# FLIC_V2.net
KiCad netlist of a schematic drawn in EAGLE
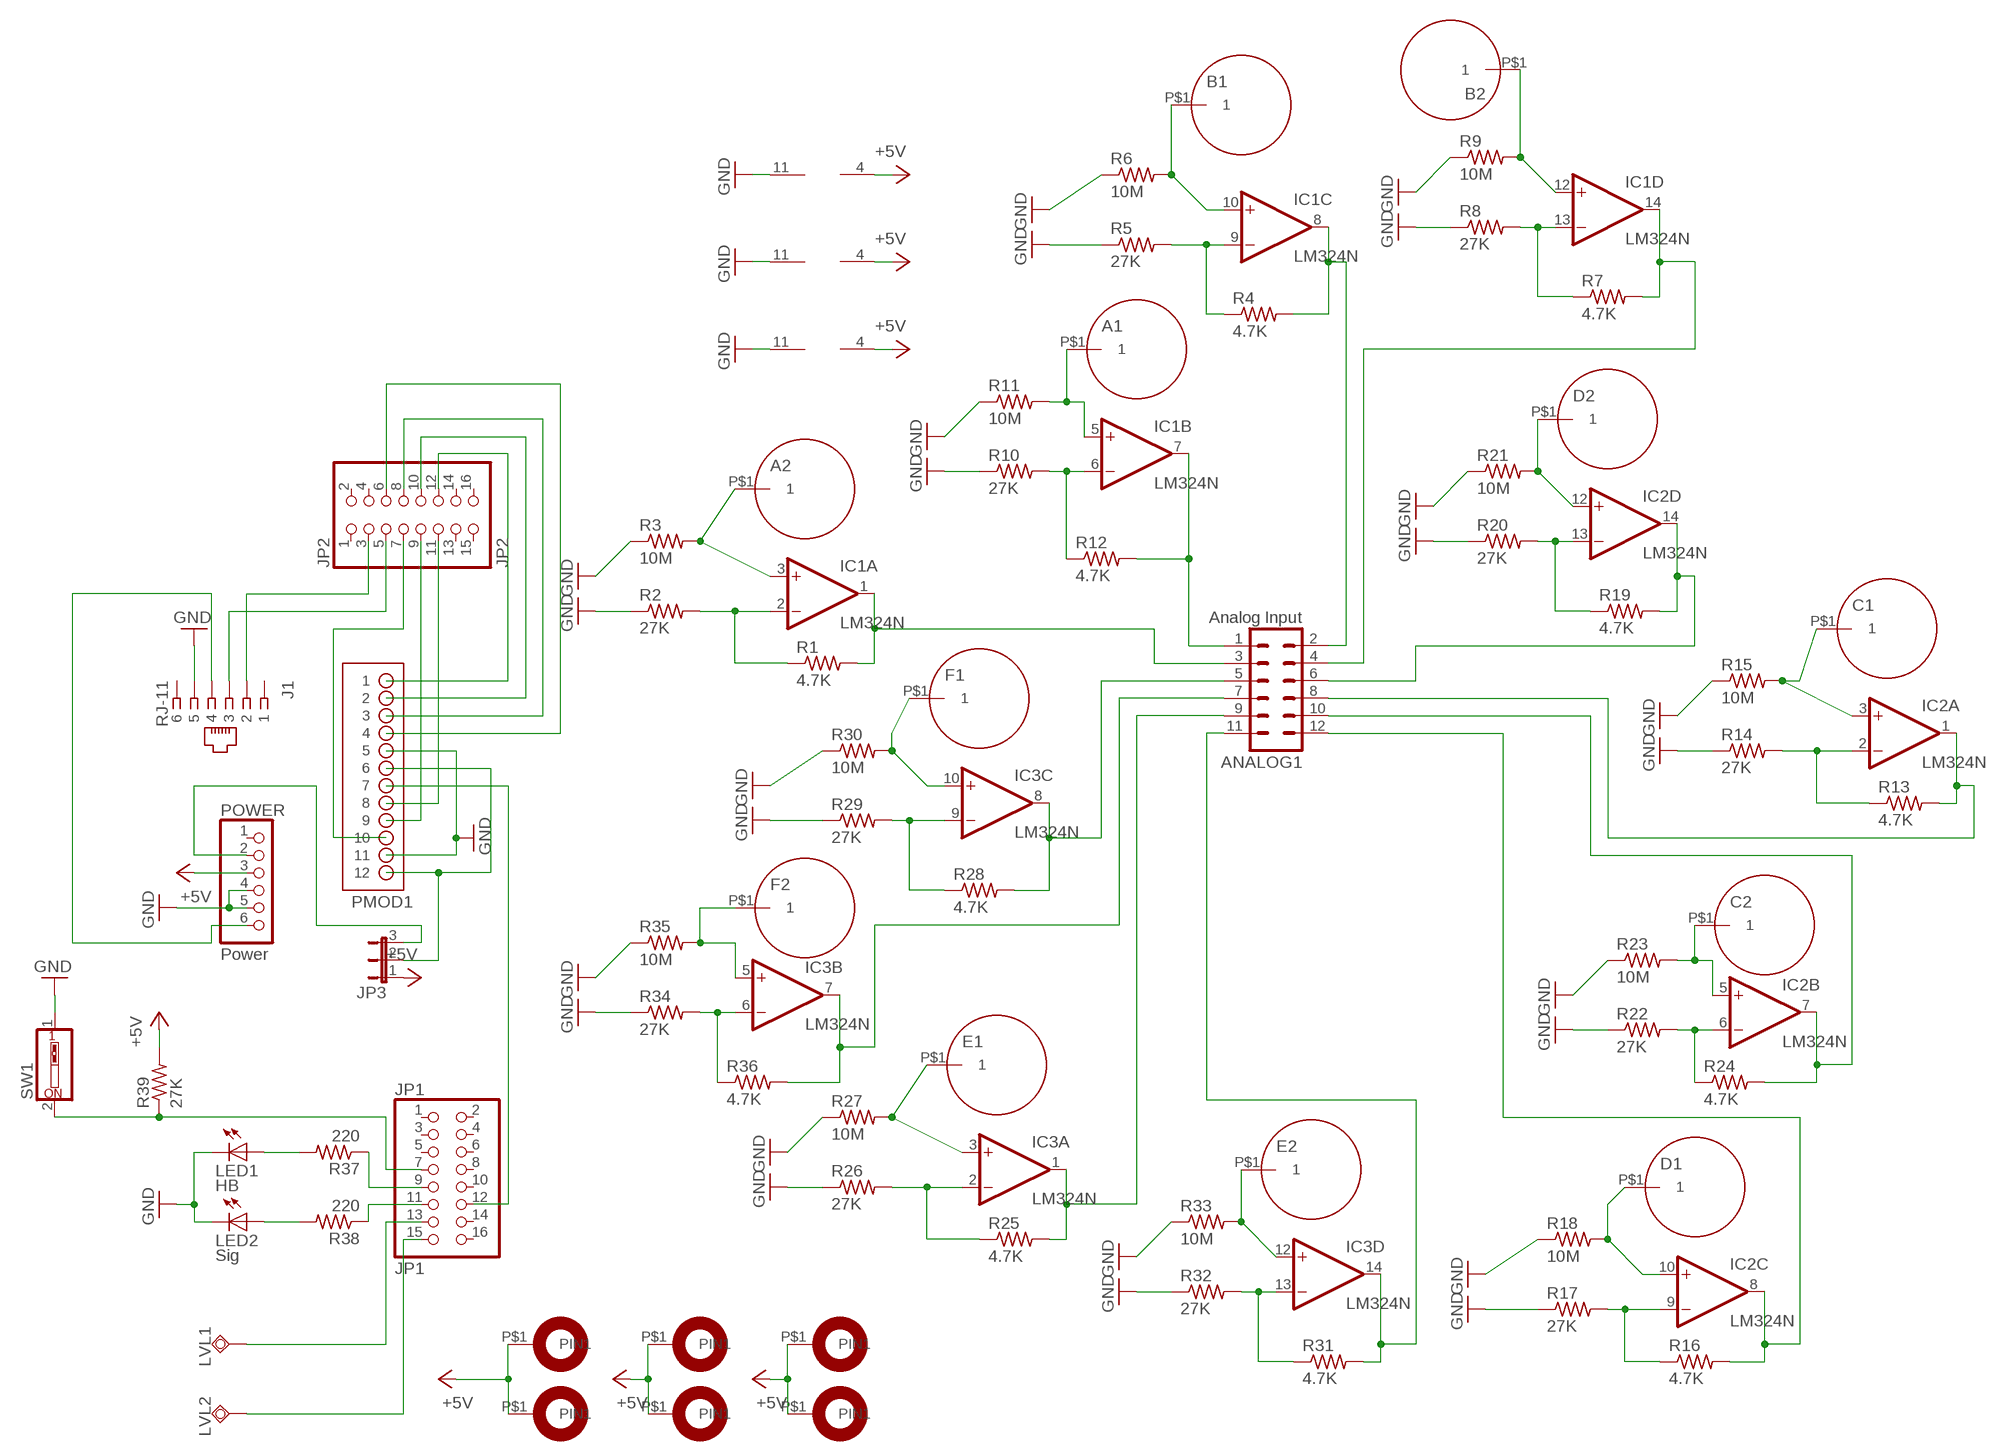
[diagram p0: schematic, sheet 1]

(export (version "E")
  (design (tool "Eeschema 10.0.6"))
  (components
    (comp (ref "A1")
      (value "FLIC_PADPAD")
      (footprint "eagle-import:FLICPAD")
      (libsource (lib "eagle-import") (part "FLIC_PADPAD"))
    )
    (comp (ref "A2")
      (value "FLIC_PADPAD")
      (footprint "eagle-import:FLICPAD")
      (libsource (lib "eagle-import") (part "FLIC_PADPAD"))
    )
    (comp (ref "ANALOG1")
      (value "Analog Input")
      (footprint "eagle-import:MA06-2")
      (libsource (lib "eagle-import") (part "MA06-2"))
    )
    (comp (ref "B1")
      (value "FLIC_PADPAD")
      (footprint "eagle-import:FLICPAD")
      (libsource (lib "eagle-import") (part "FLIC_PADPAD"))
    )
    (comp (ref "B2")
      (value "FLIC_PADPAD")
      (footprint "eagle-import:FLICPAD")
      (libsource (lib "eagle-import") (part "FLIC_PADPAD"))
    )
    (comp (ref "C1")
      (value "FLIC_PADPAD")
      (footprint "eagle-import:FLICPAD")
      (libsource (lib "eagle-import") (part "FLIC_PADPAD"))
    )
    (comp (ref "C2")
      (value "FLIC_PADPAD")
      (footprint "eagle-import:FLICPAD")
      (libsource (lib "eagle-import") (part "FLIC_PADPAD"))
    )
    (comp (ref "D1")
      (value "FLIC_PADPAD")
      (footprint "eagle-import:FLICPAD")
      (libsource (lib "eagle-import") (part "FLIC_PADPAD"))
    )
    (comp (ref "D2")
      (value "FLIC_PADPAD")
      (footprint "eagle-import:FLICPAD")
      (libsource (lib "eagle-import") (part "FLIC_PADPAD"))
    )
    (comp (ref "E1")
      (value "FLIC_PADPAD")
      (footprint "eagle-import:FLICPAD")
      (libsource (lib "eagle-import") (part "FLIC_PADPAD"))
    )
    (comp (ref "E2")
      (value "FLIC_PADPAD")
      (footprint "eagle-import:FLICPAD")
      (libsource (lib "eagle-import") (part "FLIC_PADPAD"))
    )
    (comp (ref "F1")
      (value "FLIC_PADPAD")
      (footprint "eagle-import:FLICPAD")
      (libsource (lib "eagle-import") (part "FLIC_PADPAD"))
    )
    (comp (ref "F2")
      (value "FLIC_PADPAD")
      (footprint "eagle-import:FLICPAD")
      (libsource (lib "eagle-import") (part "FLIC_PADPAD"))
    )
    (comp (ref "IC1")
      (value "LM324N")
      (footprint "eagle-import:DIL14")
      (libsource (lib "eagle-import") (part "LM324N"))
    )
    (comp (ref "IC2")
      (value "LM324N")
      (footprint "eagle-import:DIL14")
      (libsource (lib "eagle-import") (part "LM324N"))
    )
    (comp (ref "IC3")
      (value "LM324N")
      (footprint "eagle-import:DIL14")
      (libsource (lib "eagle-import") (part "LM324N"))
    )
    (comp (ref "J1")
      (value "RJ-11")
      (footprint "eagle-import:RJ11-NO_SHIELD")
      (fields (field (name "MF") "TYCO ELECTRONICS") (field (name "MPN") "RJ11-2L-B"))
      (libsource (lib "eagle-import") (part "RJ11-2L-B"))
    )
    (comp (ref "JP1")
      (value "JP1")
      (footprint "eagle-import:2X08")
      (libsource (lib "eagle-import") (part "PINHD-2X8"))
    )
    (comp (ref "JP2")
      (value "JP2")
      (footprint "eagle-import:2X08")
      (libsource (lib "eagle-import") (part "PINHD-2X8"))
    )
    (comp (ref "JP3")
      (value "JP2E")
      (footprint "eagle-import:JP2")
      (libsource (lib "eagle-import") (part "JP2E"))
    )
    (comp (ref "LED1")
      (value "HB")
      (footprint "eagle-import:LED3MM")
      (libsource (lib "eagle-import") (part "LED3MM"))
    )
    (comp (ref "LED2")
      (value "Sig")
      (footprint "eagle-import:LED3MM")
      (libsource (lib "eagle-import") (part "LED3MM"))
    )
    (comp (ref "LVL1")
      (value "TPSQTP20R")
      (footprint "eagle-import:TP20R")
      (libsource (lib "eagle-import") (part "TPSQTP20R"))
    )
    (comp (ref "LVL2")
      (value "TPSQTP20R")
      (footprint "eagle-import:TP20R")
      (libsource (lib "eagle-import") (part "TPSQTP20R"))
    )
    (comp (ref "PMOD1")
      (value "PMOD-2X6-S")
      (footprint "eagle-import:PMOD-2X6-S")
      (libsource (lib "eagle-import") (part "PMOD-2X6-S"))
    )
    (comp (ref "POWER")
      (value "Power")
      (footprint "eagle-import:1X06")
      (libsource (lib "eagle-import") (part "PINHD-1X6"))
    )
    (comp (ref "R1")
      (value "4.7K")
      (footprint "eagle-import:0207_10")
      (libsource (lib "eagle-import") (part "R-US_0207/10"))
    )
    (comp (ref "R2")
      (value "27K")
      (footprint "eagle-import:0207_10")
      (libsource (lib "eagle-import") (part "R-US_0207/10"))
    )
    (comp (ref "R3")
      (value "10M")
      (footprint "eagle-import:0207_10")
      (libsource (lib "eagle-import") (part "R-US_0207/10"))
    )
    (comp (ref "R4")
      (value "4.7K")
      (footprint "eagle-import:0207_10")
      (libsource (lib "eagle-import") (part "R-US_0207/10"))
    )
    (comp (ref "R5")
      (value "27K")
      (footprint "eagle-import:0207_10")
      (libsource (lib "eagle-import") (part "R-US_0207/10"))
    )
    (comp (ref "R6")
      (value "10M")
      (footprint "eagle-import:0207_10")
      (libsource (lib "eagle-import") (part "R-US_0207/10"))
    )
    (comp (ref "R7")
      (value "4.7K")
      (footprint "eagle-import:0207_10")
      (libsource (lib "eagle-import") (part "R-US_0207/10"))
    )
    (comp (ref "R8")
      (value "27K")
      (footprint "eagle-import:0207_10")
      (libsource (lib "eagle-import") (part "R-US_0207/10"))
    )
    (comp (ref "R9")
      (value "10M")
      (footprint "eagle-import:0207_10")
      (libsource (lib "eagle-import") (part "R-US_0207/10"))
    )
    (comp (ref "R10")
      (value "27K")
      (footprint "eagle-import:0207_10")
      (libsource (lib "eagle-import") (part "R-US_0207/10"))
    )
    (comp (ref "R11")
      (value "10M")
      (footprint "eagle-import:0207_10")
      (libsource (lib "eagle-import") (part "R-US_0207/10"))
    )
    (comp (ref "R12")
      (value "4.7K")
      (footprint "eagle-import:0207_10")
      (libsource (lib "eagle-import") (part "R-US_0207/10"))
    )
    (comp (ref "R13")
      (value "4.7K")
      (footprint "eagle-import:0207_10")
      (libsource (lib "eagle-import") (part "R-US_0207/10"))
    )
    (comp (ref "R14")
      (value "27K")
      (footprint "eagle-import:0207_10")
      (libsource (lib "eagle-import") (part "R-US_0207/10"))
    )
    (comp (ref "R15")
      (value "10M")
      (footprint "eagle-import:0207_10")
      (libsource (lib "eagle-import") (part "R-US_0207/10"))
    )
    (comp (ref "R16")
      (value "4.7K")
      (footprint "eagle-import:0207_10")
      (libsource (lib "eagle-import") (part "R-US_0207/10"))
    )
    (comp (ref "R17")
      (value "27K")
      (footprint "eagle-import:0207_10")
      (libsource (lib "eagle-import") (part "R-US_0207/10"))
    )
    (comp (ref "R18")
      (value "10M")
      (footprint "eagle-import:0207_10")
      (libsource (lib "eagle-import") (part "R-US_0207/10"))
    )
    (comp (ref "R19")
      (value "4.7K")
      (footprint "eagle-import:0207_10")
      (libsource (lib "eagle-import") (part "R-US_0207/10"))
    )
    (comp (ref "R20")
      (value "27K")
      (footprint "eagle-import:0207_10")
      (libsource (lib "eagle-import") (part "R-US_0207/10"))
    )
    (comp (ref "R21")
      (value "10M")
      (footprint "eagle-import:0207_10")
      (libsource (lib "eagle-import") (part "R-US_0207/10"))
    )
    (comp (ref "R22")
      (value "27K")
      (footprint "eagle-import:0207_10")
      (libsource (lib "eagle-import") (part "R-US_0207/10"))
    )
    (comp (ref "R23")
      (value "10M")
      (footprint "eagle-import:0207_10")
      (libsource (lib "eagle-import") (part "R-US_0207/10"))
    )
    (comp (ref "R24")
      (value "4.7K")
      (footprint "eagle-import:0207_10")
      (libsource (lib "eagle-import") (part "R-US_0207/10"))
    )
    (comp (ref "R25")
      (value "4.7K")
      (footprint "eagle-import:0207_10")
      (libsource (lib "eagle-import") (part "R-US_0207/10"))
    )
    (comp (ref "R26")
      (value "27K")
      (footprint "eagle-import:0207_10")
      (libsource (lib "eagle-import") (part "R-US_0207/10"))
    )
    (comp (ref "R27")
      (value "10M")
      (footprint "eagle-import:0207_10")
      (libsource (lib "eagle-import") (part "R-US_0207/10"))
    )
    (comp (ref "R28")
      (value "4.7K")
      (footprint "eagle-import:0207_10")
      (libsource (lib "eagle-import") (part "R-US_0207/10"))
    )
    (comp (ref "R29")
      (value "27K")
      (footprint "eagle-import:0207_10")
      (libsource (lib "eagle-import") (part "R-US_0207/10"))
    )
    (comp (ref "R30")
      (value "10M")
      (footprint "eagle-import:0207_10")
      (libsource (lib "eagle-import") (part "R-US_0207/10"))
    )
    (comp (ref "R31")
      (value "4.7K")
      (footprint "eagle-import:0207_10")
      (libsource (lib "eagle-import") (part "R-US_0207/10"))
    )
    (comp (ref "R32")
      (value "27K")
      (footprint "eagle-import:0207_10")
      (libsource (lib "eagle-import") (part "R-US_0207/10"))
    )
    (comp (ref "R33")
      (value "10M")
      (footprint "eagle-import:0207_10")
      (libsource (lib "eagle-import") (part "R-US_0207/10"))
    )
    (comp (ref "R34")
      (value "27K")
      (footprint "eagle-import:0207_10")
      (libsource (lib "eagle-import") (part "R-US_0207/10"))
    )
    (comp (ref "R35")
      (value "10M")
      (footprint "eagle-import:0207_10")
      (libsource (lib "eagle-import") (part "R-US_0207/10"))
    )
    (comp (ref "R36")
      (value "4.7K")
      (footprint "eagle-import:0207_10")
      (libsource (lib "eagle-import") (part "R-US_0207/10"))
    )
    (comp (ref "R37")
      (value "220")
      (footprint "eagle-import:0207_10")
      (libsource (lib "eagle-import") (part "R-US_0207/10"))
    )
    (comp (ref "R38")
      (value "220")
      (footprint "eagle-import:0207_10")
      (libsource (lib "eagle-import") (part "R-US_0207/10"))
    )
    (comp (ref "R39")
      (value "27K")
      (footprint "eagle-import:0207_10")
      (libsource (lib "eagle-import") (part "R-US_0207/10"))
    )
    (comp (ref "SW1")
      (value "SW_DIP-1")
      (footprint "eagle-import:EDG-01")
      (libsource (lib "eagle-import") (part "SW_DIP-1"))
    )
    (comp (ref "U$1")
      (value "4MM_HOLEA")
      (footprint "eagle-import:4MM")
      (libsource (lib "eagle-import") (part "4MM_HOLEA"))
    )
    (comp (ref "U$2")
      (value "4MM_HOLEA")
      (footprint "eagle-import:4MM")
      (libsource (lib "eagle-import") (part "4MM_HOLEA"))
    )
    (comp (ref "U$3")
      (value "4MM_HOLEA")
      (footprint "eagle-import:4MM")
      (libsource (lib "eagle-import") (part "4MM_HOLEA"))
    )
    (comp (ref "U$4")
      (value "4MM_HOLEA")
      (footprint "eagle-import:4MM")
      (libsource (lib "eagle-import") (part "4MM_HOLEA"))
    )
    (comp (ref "U$5")
      (value "4MM_HOLEA")
      (footprint "eagle-import:4MM")
      (libsource (lib "eagle-import") (part "4MM_HOLEA"))
    )
    (comp (ref "U$6")
      (value "4MM_HOLEA")
      (footprint "eagle-import:4MM")
      (libsource (lib "eagle-import") (part "4MM_HOLEA"))
    )
  )
  (nets
    (net (code "1") (name "+5V") (class "Default")
      (node (ref "IC1") (pin "4") (pinfunction "V+_4") (pintype "power_in"))
      (node (ref "IC2") (pin "4") (pinfunction "V+_4") (pintype "power_in"))
      (node (ref "IC3") (pin "4") (pinfunction "V+_4") (pintype "power_in"))
      (node (ref "JP3") (pin "1") (pinfunction "1_1") (pintype "passive"))
      (node (ref "POWER") (pin "3") (pinfunction "3_3") (pintype "passive"))
      (node (ref "R39") (pin "2") (pinfunction "2_2") (pintype "passive"))
      (node (ref "U$1") (pin "P$1") (pinfunction "PIN1_P$1") (pintype "bidirectional"))
      (node (ref "U$2") (pin "P$1") (pinfunction "PIN1_P$1") (pintype "bidirectional"))
      (node (ref "U$3") (pin "P$1") (pinfunction "PIN1_P$1") (pintype "bidirectional"))
      (node (ref "U$4") (pin "P$1") (pinfunction "PIN1_P$1") (pintype "bidirectional"))
      (node (ref "U$5") (pin "P$1") (pinfunction "PIN1_P$1") (pintype "bidirectional"))
      (node (ref "U$6") (pin "P$1") (pinfunction "PIN1_P$1") (pintype "bidirectional"))
    )
    (net (code "2") (name "GND") (class "Default")
      (node (ref "IC1") (pin "11") (pinfunction "V-_11") (pintype "power_in"))
      (node (ref "IC2") (pin "11") (pinfunction "V-_11") (pintype "power_in"))
      (node (ref "IC3") (pin "11") (pinfunction "V-_11") (pintype "power_in"))
      (node (ref "J1") (pin "5") (pinfunction "5_5") (pintype "passive"))
      (node (ref "LED1") (pin "K") (pinfunction "C_K") (pintype "passive"))
      (node (ref "LED2") (pin "K") (pinfunction "C_K") (pintype "passive"))
      (node (ref "PMOD1") (pin "11") (pinfunction "11_11") (pintype "passive"))
      (node (ref "PMOD1") (pin "5") (pinfunction "5_5") (pintype "passive"))
      (node (ref "POWER") (pin "4") (pinfunction "4_4") (pintype "passive"))
      (node (ref "POWER") (pin "5") (pinfunction "5_5") (pintype "passive"))
      (node (ref "R10") (pin "1") (pinfunction "1_1") (pintype "passive"))
      (node (ref "R11") (pin "1") (pinfunction "1_1") (pintype "passive"))
      (node (ref "R14") (pin "1") (pinfunction "1_1") (pintype "passive"))
      (node (ref "R15") (pin "1") (pinfunction "1_1") (pintype "passive"))
      (node (ref "R17") (pin "1") (pinfunction "1_1") (pintype "passive"))
      (node (ref "R18") (pin "1") (pinfunction "1_1") (pintype "passive"))
      (node (ref "R2") (pin "1") (pinfunction "1_1") (pintype "passive"))
      (node (ref "R20") (pin "1") (pinfunction "1_1") (pintype "passive"))
      (node (ref "R21") (pin "1") (pinfunction "1_1") (pintype "passive"))
      (node (ref "R22") (pin "1") (pinfunction "1_1") (pintype "passive"))
      (node (ref "R23") (pin "1") (pinfunction "1_1") (pintype "passive"))
      (node (ref "R26") (pin "1") (pinfunction "1_1") (pintype "passive"))
      (node (ref "R27") (pin "1") (pinfunction "1_1") (pintype "passive"))
      (node (ref "R29") (pin "1") (pinfunction "1_1") (pintype "passive"))
      (node (ref "R3") (pin "1") (pinfunction "1_1") (pintype "passive"))
      (node (ref "R30") (pin "1") (pinfunction "1_1") (pintype "passive"))
      (node (ref "R32") (pin "1") (pinfunction "1_1") (pintype "passive"))
      (node (ref "R33") (pin "1") (pinfunction "1_1") (pintype "passive"))
      (node (ref "R34") (pin "1") (pinfunction "1_1") (pintype "passive"))
      (node (ref "R35") (pin "1") (pinfunction "1_1") (pintype "passive"))
      (node (ref "R5") (pin "1") (pinfunction "1_1") (pintype "passive"))
      (node (ref "R6") (pin "1") (pinfunction "1_1") (pintype "passive"))
      (node (ref "R8") (pin "1") (pinfunction "1_1") (pintype "passive"))
      (node (ref "R9") (pin "1") (pinfunction "1_1") (pintype "passive"))
      (node (ref "SW1") (pin "1") (pinfunction "1_1") (pintype "passive"))
    )
    (net (code "3") (name "Net-(A1-1)") (class "Default")
      (node (ref "A1") (pin "P$1") (pinfunction "1_P$1") (pintype "passive"))
      (node (ref "IC1") (pin "5") (pinfunction "+IN_5") (pintype "input"))
      (node (ref "R11") (pin "2") (pinfunction "2_2") (pintype "passive"))
    )
    (net (code "4") (name "Net-(A2-1)") (class "Default")
      (node (ref "A2") (pin "P$1") (pinfunction "1_P$1") (pintype "passive"))
      (node (ref "IC1") (pin "3") (pinfunction "+IN_3") (pintype "input"))
      (node (ref "R3") (pin "2") (pinfunction "2_2") (pintype "passive"))
    )
    (net (code "5") (name "Net-(B1-1)") (class "Default")
      (node (ref "B1") (pin "P$1") (pinfunction "1_P$1") (pintype "passive"))
      (node (ref "IC1") (pin "10") (pinfunction "+IN_10") (pintype "input"))
      (node (ref "R6") (pin "2") (pinfunction "2_2") (pintype "passive"))
    )
    (net (code "6") (name "Net-(B2-1)") (class "Default")
      (node (ref "B2") (pin "P$1") (pinfunction "1_P$1") (pintype "passive"))
      (node (ref "IC1") (pin "12") (pinfunction "+IN_12") (pintype "input"))
      (node (ref "R9") (pin "2") (pinfunction "2_2") (pintype "passive"))
    )
    (net (code "7") (name "Net-(C1-1)") (class "Default")
      (node (ref "C1") (pin "P$1") (pinfunction "1_P$1") (pintype "passive"))
      (node (ref "IC2") (pin "3") (pinfunction "+IN_3") (pintype "input"))
      (node (ref "R15") (pin "2") (pinfunction "2_2") (pintype "passive"))
    )
    (net (code "8") (name "Net-(C2-1)") (class "Default")
      (node (ref "C2") (pin "P$1") (pinfunction "1_P$1") (pintype "passive"))
      (node (ref "IC2") (pin "5") (pinfunction "+IN_5") (pintype "input"))
      (node (ref "R23") (pin "2") (pinfunction "2_2") (pintype "passive"))
    )
    (net (code "9") (name "Net-(D1-1)") (class "Default")
      (node (ref "D1") (pin "P$1") (pinfunction "1_P$1") (pintype "passive"))
      (node (ref "IC2") (pin "10") (pinfunction "+IN_10") (pintype "input"))
      (node (ref "R18") (pin "2") (pinfunction "2_2") (pintype "passive"))
    )
    (net (code "10") (name "Net-(D2-1)") (class "Default")
      (node (ref "D2") (pin "P$1") (pinfunction "1_P$1") (pintype "passive"))
      (node (ref "IC2") (pin "12") (pinfunction "+IN_12") (pintype "input"))
      (node (ref "R21") (pin "2") (pinfunction "2_2") (pintype "passive"))
    )
    (net (code "11") (name "Net-(E1-1)") (class "Default")
      (node (ref "E1") (pin "P$1") (pinfunction "1_P$1") (pintype "passive"))
      (node (ref "IC3") (pin "3") (pinfunction "+IN_3") (pintype "input"))
      (node (ref "R27") (pin "2") (pinfunction "2_2") (pintype "passive"))
    )
    (net (code "12") (name "Net-(E2-1)") (class "Default")
      (node (ref "E2") (pin "P$1") (pinfunction "1_P$1") (pintype "passive"))
      (node (ref "IC3") (pin "12") (pinfunction "+IN_12") (pintype "input"))
      (node (ref "R33") (pin "2") (pinfunction "2_2") (pintype "passive"))
    )
    (net (code "13") (name "Net-(F1-1)") (class "Default")
      (node (ref "F1") (pin "P$1") (pinfunction "1_P$1") (pintype "passive"))
      (node (ref "IC3") (pin "10") (pinfunction "+IN_10") (pintype "input"))
      (node (ref "R30") (pin "2") (pinfunction "2_2") (pintype "passive"))
    )
    (net (code "14") (name "Net-(F2-1)") (class "Default")
      (node (ref "F2") (pin "P$1") (pinfunction "1_P$1") (pintype "passive"))
      (node (ref "IC3") (pin "5") (pinfunction "+IN_5") (pintype "input"))
      (node (ref "R35") (pin "2") (pinfunction "2_2") (pintype "passive"))
    )
    (net (code "15") (name "Net-(IC1A--IN)") (class "Default")
      (node (ref "IC1") (pin "2") (pinfunction "-IN_2") (pintype "input"))
      (node (ref "R1") (pin "1") (pinfunction "1_1") (pintype "passive"))
      (node (ref "R2") (pin "2") (pinfunction "2_2") (pintype "passive"))
    )
    (net (code "16") (name "Net-(IC1A-OUT)") (class "Default")
      (node (ref "ANALOG1") (pin "3") (pinfunction "3_3") (pintype "passive"))
      (node (ref "IC1") (pin "1") (pinfunction "OUT_1") (pintype "output"))
      (node (ref "R1") (pin "2") (pinfunction "2_2") (pintype "passive"))
    )
    (net (code "17") (name "Net-(IC1B--IN)") (class "Default")
      (node (ref "IC1") (pin "6") (pinfunction "-IN_6") (pintype "input"))
      (node (ref "R10") (pin "2") (pinfunction "2_2") (pintype "passive"))
      (node (ref "R12") (pin "1") (pinfunction "1_1") (pintype "passive"))
    )
    (net (code "18") (name "Net-(IC1B-OUT)") (class "Default")
      (node (ref "ANALOG1") (pin "1") (pinfunction "1_1") (pintype "passive"))
      (node (ref "IC1") (pin "7") (pinfunction "OUT_7") (pintype "output"))
      (node (ref "R12") (pin "2") (pinfunction "2_2") (pintype "passive"))
    )
    (net (code "19") (name "Net-(IC1C--IN)") (class "Default")
      (node (ref "IC1") (pin "9") (pinfunction "-IN_9") (pintype "input"))
      (node (ref "R4") (pin "1") (pinfunction "1_1") (pintype "passive"))
      (node (ref "R5") (pin "2") (pinfunction "2_2") (pintype "passive"))
    )
    (net (code "20") (name "Net-(IC1C-OUT)") (class "Default")
      (node (ref "ANALOG1") (pin "2") (pinfunction "2_2") (pintype "passive"))
      (node (ref "IC1") (pin "8") (pinfunction "OUT_8") (pintype "output"))
      (node (ref "R4") (pin "2") (pinfunction "2_2") (pintype "passive"))
    )
    (net (code "21") (name "Net-(IC1D--IN)") (class "Default")
      (node (ref "IC1") (pin "13") (pinfunction "-IN_13") (pintype "input"))
      (node (ref "R7") (pin "1") (pinfunction "1_1") (pintype "passive"))
      (node (ref "R8") (pin "2") (pinfunction "2_2") (pintype "passive"))
    )
    (net (code "22") (name "Net-(IC1D-OUT)") (class "Default")
      (node (ref "ANALOG1") (pin "4") (pinfunction "4_4") (pintype "passive"))
      (node (ref "IC1") (pin "14") (pinfunction "OUT_14") (pintype "output"))
      (node (ref "R7") (pin "2") (pinfunction "2_2") (pintype "passive"))
    )
    (net (code "23") (name "Net-(IC2A--IN)") (class "Default")
      (node (ref "IC2") (pin "2") (pinfunction "-IN_2") (pintype "input"))
      (node (ref "R13") (pin "1") (pinfunction "1_1") (pintype "passive"))
      (node (ref "R14") (pin "2") (pinfunction "2_2") (pintype "passive"))
    )
    (net (code "24") (name "Net-(IC2A-OUT)") (class "Default")
      (node (ref "ANALOG1") (pin "8") (pinfunction "8_8") (pintype "passive"))
      (node (ref "IC2") (pin "1") (pinfunction "OUT_1") (pintype "output"))
      (node (ref "R13") (pin "2") (pinfunction "2_2") (pintype "passive"))
    )
    (net (code "25") (name "Net-(IC2B--IN)") (class "Default")
      (node (ref "IC2") (pin "6") (pinfunction "-IN_6") (pintype "input"))
      (node (ref "R22") (pin "2") (pinfunction "2_2") (pintype "passive"))
      (node (ref "R24") (pin "1") (pinfunction "1_1") (pintype "passive"))
    )
    (net (code "26") (name "Net-(IC2B-OUT)") (class "Default")
      (node (ref "ANALOG1") (pin "10") (pinfunction "10_10") (pintype "passive"))
      (node (ref "IC2") (pin "7") (pinfunction "OUT_7") (pintype "output"))
      (node (ref "R24") (pin "2") (pinfunction "2_2") (pintype "passive"))
    )
    (net (code "27") (name "Net-(IC2C--IN)") (class "Default")
      (node (ref "IC2") (pin "9") (pinfunction "-IN_9") (pintype "input"))
      (node (ref "R16") (pin "1") (pinfunction "1_1") (pintype "passive"))
      (node (ref "R17") (pin "2") (pinfunction "2_2") (pintype "passive"))
    )
    (net (code "28") (name "Net-(IC2C-OUT)") (class "Default")
      (node (ref "ANALOG1") (pin "12") (pinfunction "12_12") (pintype "passive"))
      (node (ref "IC2") (pin "8") (pinfunction "OUT_8") (pintype "output"))
      (node (ref "R16") (pin "2") (pinfunction "2_2") (pintype "passive"))
    )
    (net (code "29") (name "Net-(IC2D--IN)") (class "Default")
      (node (ref "IC2") (pin "13") (pinfunction "-IN_13") (pintype "input"))
      (node (ref "R19") (pin "1") (pinfunction "1_1") (pintype "passive"))
      (node (ref "R20") (pin "2") (pinfunction "2_2") (pintype "passive"))
    )
    (net (code "30") (name "Net-(IC2D-OUT)") (class "Default")
      (node (ref "ANALOG1") (pin "6") (pinfunction "6_6") (pintype "passive"))
      (node (ref "IC2") (pin "14") (pinfunction "OUT_14") (pintype "output"))
      (node (ref "R19") (pin "2") (pinfunction "2_2") (pintype "passive"))
    )
    (net (code "31") (name "Net-(IC3A--IN)") (class "Default")
      (node (ref "IC3") (pin "2") (pinfunction "-IN_2") (pintype "input"))
      (node (ref "R25") (pin "1") (pinfunction "1_1") (pintype "passive"))
      (node (ref "R26") (pin "2") (pinfunction "2_2") (pintype "passive"))
    )
    (net (code "32") (name "Net-(IC3A-OUT)") (class "Default")
      (node (ref "ANALOG1") (pin "9") (pinfunction "9_9") (pintype "passive"))
      (node (ref "IC3") (pin "1") (pinfunction "OUT_1") (pintype "output"))
      (node (ref "R25") (pin "2") (pinfunction "2_2") (pintype "passive"))
    )
    (net (code "33") (name "Net-(IC3B--IN)") (class "Default")
      (node (ref "IC3") (pin "6") (pinfunction "-IN_6") (pintype "input"))
      (node (ref "R34") (pin "2") (pinfunction "2_2") (pintype "passive"))
      (node (ref "R36") (pin "1") (pinfunction "1_1") (pintype "passive"))
    )
    (net (code "34") (name "Net-(IC3B-OUT)") (class "Default")
      (node (ref "ANALOG1") (pin "7") (pinfunction "7_7") (pintype "passive"))
      (node (ref "IC3") (pin "7") (pinfunction "OUT_7") (pintype "output"))
      (node (ref "R36") (pin "2") (pinfunction "2_2") (pintype "passive"))
    )
    (net (code "35") (name "Net-(IC3C--IN)") (class "Default")
      (node (ref "IC3") (pin "9") (pinfunction "-IN_9") (pintype "input"))
      (node (ref "R28") (pin "1") (pinfunction "1_1") (pintype "passive"))
      (node (ref "R29") (pin "2") (pinfunction "2_2") (pintype "passive"))
    )
    (net (code "36") (name "Net-(IC3C-OUT)") (class "Default")
      (node (ref "ANALOG1") (pin "5") (pinfunction "5_5") (pintype "passive"))
      (node (ref "IC3") (pin "8") (pinfunction "OUT_8") (pintype "output"))
      (node (ref "R28") (pin "2") (pinfunction "2_2") (pintype "passive"))
    )
    (net (code "37") (name "Net-(IC3D--IN)") (class "Default")
      (node (ref "IC3") (pin "13") (pinfunction "-IN_13") (pintype "input"))
      (node (ref "R31") (pin "1") (pinfunction "1_1") (pintype "passive"))
      (node (ref "R32") (pin "2") (pinfunction "2_2") (pintype "passive"))
    )
    (net (code "38") (name "Net-(IC3D-OUT)") (class "Default")
      (node (ref "ANALOG1") (pin "11") (pinfunction "11_11") (pintype "passive"))
      (node (ref "IC3") (pin "14") (pinfunction "OUT_14") (pintype "output"))
      (node (ref "R31") (pin "2") (pinfunction "2_2") (pintype "passive"))
    )
    (net (code "39") (name "Net-(J1-Pad2)") (class "Default")
      (node (ref "J1") (pin "2") (pinfunction "2_2") (pintype "passive"))
      (node (ref "JP2") (pin "3") (pinfunction "3_3") (pintype "passive"))
    )
    (net (code "40") (name "Net-(J1-Pad3)") (class "Default")
      (node (ref "J1") (pin "3") (pinfunction "3_3") (pintype "passive"))
      (node (ref "JP2") (pin "5") (pinfunction "5_5") (pintype "passive"))
    )
    (net (code "41") (name "Net-(J1-Pad4)") (class "Default")
      (node (ref "J1") (pin "4") (pinfunction "4_4") (pintype "passive"))
      (node (ref "POWER") (pin "6") (pinfunction "6_6") (pintype "passive"))
    )
    (net (code "42") (name "Net-(JP1-Pad7)") (class "Default")
      (node (ref "JP1") (pin "7") (pinfunction "7_7") (pintype "passive"))
      (node (ref "R39") (pin "1") (pinfunction "1_1") (pintype "passive"))
      (node (ref "SW1") (pin "2") (pinfunction "2_2") (pintype "passive"))
    )
    (net (code "43") (name "Net-(JP1-Pad9)") (class "Default")
      (node (ref "JP1") (pin "9") (pinfunction "9_9") (pintype "passive"))
      (node (ref "R37") (pin "1") (pinfunction "1_1") (pintype "passive"))
    )
    (net (code "44") (name "Net-(JP1-Pad11)") (class "Default")
      (node (ref "JP1") (pin "11") (pinfunction "11_11") (pintype "passive"))
      (node (ref "R38") (pin "1") (pinfunction "1_1") (pintype "passive"))
    )
    (net (code "45") (name "Net-(JP1-Pad12)") (class "Default")
      (node (ref "JP1") (pin "12") (pinfunction "12_12") (pintype "passive"))
      (node (ref "PMOD1") (pin "7") (pinfunction "7_7") (pintype "passive"))
    )
    (net (code "46") (name "Net-(JP1-Pad13)") (class "Default")
      (node (ref "JP1") (pin "13") (pinfunction "13_13") (pintype "passive"))
      (node (ref "LVL1") (pin "TP") (pinfunction "TP_TP") (pintype "input"))
    )
    (net (code "47") (name "Net-(JP1-Pad15)") (class "Default")
      (node (ref "JP1") (pin "15") (pinfunction "15_15") (pintype "passive"))
      (node (ref "LVL2") (pin "TP") (pinfunction "TP_TP") (pintype "input"))
    )
    (net (code "48") (name "Net-(JP2-Pad6)") (class "Default")
      (node (ref "JP2") (pin "6") (pinfunction "6_6") (pintype "passive"))
      (node (ref "PMOD1") (pin "4") (pinfunction "4_4") (pintype "passive"))
    )
    (net (code "49") (name "Net-(JP2-Pad7)") (class "Default")
      (node (ref "JP2") (pin "7") (pinfunction "7_7") (pintype "passive"))
      (node (ref "PMOD1") (pin "10") (pinfunction "10_10") (pintype "passive"))
    )
    (net (code "50") (name "Net-(JP2-Pad8)") (class "Default")
      (node (ref "JP2") (pin "8") (pinfunction "8_8") (pintype "passive"))
      (node (ref "PMOD1") (pin "3") (pinfunction "3_3") (pintype "passive"))
    )
    (net (code "51") (name "Net-(JP2-Pad9)") (class "Default")
      (node (ref "JP2") (pin "9") (pinfunction "9_9") (pintype "passive"))
      (node (ref "PMOD1") (pin "9") (pinfunction "9_9") (pintype "passive"))
    )
    (net (code "52") (name "Net-(JP2-Pad10)") (class "Default")
      (node (ref "JP2") (pin "10") (pinfunction "10_10") (pintype "passive"))
      (node (ref "PMOD1") (pin "2") (pinfunction "2_2") (pintype "passive"))
    )
    (net (code "53") (name "Net-(JP2-Pad11)") (class "Default")
      (node (ref "JP2") (pin "11") (pinfunction "11_11") (pintype "passive"))
      (node (ref "PMOD1") (pin "8") (pinfunction "8_8") (pintype "passive"))
    )
    (net (code "54") (name "Net-(JP2-Pad12)") (class "Default")
      (node (ref "JP2") (pin "12") (pinfunction "12_12") (pintype "passive"))
      (node (ref "PMOD1") (pin "1") (pinfunction "1_1") (pintype "passive"))
    )
    (net (code "55") (name "Net-(JP3-Pad2)") (class "Default")
      (node (ref "JP3") (pin "2") (pinfunction "2_2") (pintype "passive"))
      (node (ref "PMOD1") (pin "12") (pinfunction "12_12") (pintype "passive"))
      (node (ref "PMOD1") (pin "6") (pinfunction "6_6") (pintype "passive"))
    )
    (net (code "56") (name "Net-(JP3-Pad3)") (class "Default")
      (node (ref "JP3") (pin "3") (pinfunction "3_3") (pintype "passive"))
      (node (ref "POWER") (pin "2") (pinfunction "2_2") (pintype "passive"))
    )
    (net (code "57") (name "Net-(LED1-PadA)") (class "Default")
      (node (ref "LED1") (pin "A") (pinfunction "A_A") (pintype "passive"))
      (node (ref "R37") (pin "2") (pinfunction "2_2") (pintype "passive"))
    )
    (net (code "58") (name "Net-(LED2-PadA)") (class "Default")
      (node (ref "LED2") (pin "A") (pinfunction "A_A") (pintype "passive"))
      (node (ref "R38") (pin "2") (pinfunction "2_2") (pintype "passive"))
    )
    (net (code "59") (name "unconnected-(J1-Pad1)") (class "Default")
      (node (ref "J1") (pin "1") (pinfunction "1_1") (pintype "passive"))
    )
    (net (code "60") (name "unconnected-(J1-Pad6)") (class "Default")
      (node (ref "J1") (pin "6") (pinfunction "6_6") (pintype "passive"))
    )
    (net (code "61") (name "unconnected-(JP1-Pad1)") (class "Default")
      (node (ref "JP1") (pin "1") (pinfunction "1_1") (pintype "passive"))
    )
    (net (code "62") (name "unconnected-(JP1-Pad2)") (class "Default")
      (node (ref "JP1") (pin "2") (pinfunction "2_2") (pintype "passive"))
    )
    (net (code "63") (name "unconnected-(JP1-Pad3)") (class "Default")
      (node (ref "JP1") (pin "3") (pinfunction "3_3") (pintype "passive"))
    )
    (net (code "64") (name "unconnected-(JP1-Pad4)") (class "Default")
      (node (ref "JP1") (pin "4") (pinfunction "4_4") (pintype "passive"))
    )
    (net (code "65") (name "unconnected-(JP1-Pad5)") (class "Default")
      (node (ref "JP1") (pin "5") (pinfunction "5_5") (pintype "passive"))
    )
    (net (code "66") (name "unconnected-(JP1-Pad6)") (class "Default")
      (node (ref "JP1") (pin "6") (pinfunction "6_6") (pintype "passive"))
    )
    (net (code "67") (name "unconnected-(JP1-Pad8)") (class "Default")
      (node (ref "JP1") (pin "8") (pinfunction "8_8") (pintype "passive"))
    )
    (net (code "68") (name "unconnected-(JP1-Pad10)") (class "Default")
      (node (ref "JP1") (pin "10") (pinfunction "10_10") (pintype "passive"))
    )
    (net (code "69") (name "unconnected-(JP1-Pad14)") (class "Default")
      (node (ref "JP1") (pin "14") (pinfunction "14_14") (pintype "passive"))
    )
    (net (code "70") (name "unconnected-(JP1-Pad16)") (class "Default")
      (node (ref "JP1") (pin "16") (pinfunction "16_16") (pintype "passive"))
    )
    (net (code "71") (name "unconnected-(JP2-Pad1)") (class "Default")
      (node (ref "JP2") (pin "1") (pinfunction "1_1") (pintype "passive"))
    )
    (net (code "72") (name "unconnected-(JP2-Pad2)") (class "Default")
      (node (ref "JP2") (pin "2") (pinfunction "2_2") (pintype "passive"))
    )
    (net (code "73") (name "unconnected-(JP2-Pad4)") (class "Default")
      (node (ref "JP2") (pin "4") (pinfunction "4_4") (pintype "passive"))
    )
    (net (code "74") (name "unconnected-(JP2-Pad13)") (class "Default")
      (node (ref "JP2") (pin "13") (pinfunction "13_13") (pintype "passive"))
    )
    (net (code "75") (name "unconnected-(JP2-Pad14)") (class "Default")
      (node (ref "JP2") (pin "14") (pinfunction "14_14") (pintype "passive"))
    )
    (net (code "76") (name "unconnected-(JP2-Pad15)") (class "Default")
      (node (ref "JP2") (pin "15") (pinfunction "15_15") (pintype "passive"))
    )
    (net (code "77") (name "unconnected-(JP2-Pad16)") (class "Default")
      (node (ref "JP2") (pin "16") (pinfunction "16_16") (pintype "passive"))
    )
    (net (code "78") (name "unconnected-(POWER-Pad1)") (class "Default")
      (node (ref "POWER") (pin "1") (pinfunction "1_1") (pintype "passive"))
    )
  )
)
